# 3_BLE-T3-mcu.net
KiCad netlist of a schematic drawn in Altium Designer
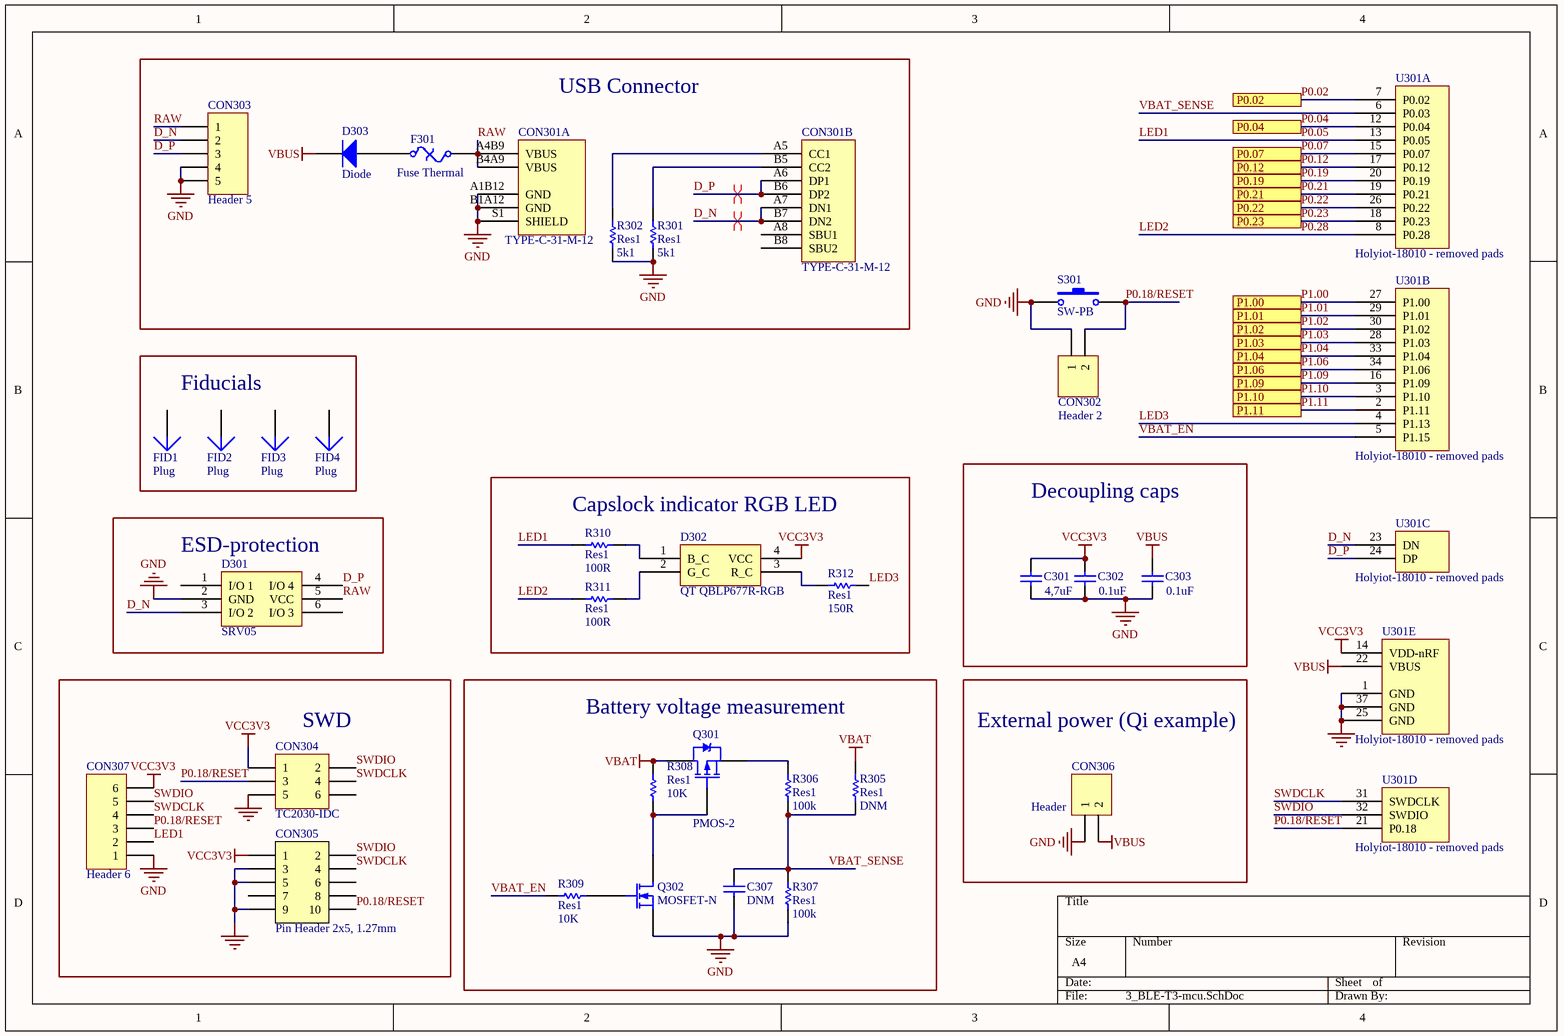
[diagram p0: 3_BLE-T3-mcu.SchDoc]

(export (version "E")
  (design (tool "Eeschema 10.0.6"))
  (components
    (comp (ref "C301")
      (value "4,7uF")
      (footprint "C0603[1608]")
      (description "Capacitor")
      (fields (field (name "LCSC PART #") "C19666") (field (name "MRF.PART") "CL10A475KO8NNNC"))
      (libsource (lib "Miscellaneous Devices") (part "Cap"))
    )
    (comp (ref "C302")
      (value "0.1uF")
      (footprint "C0603[1608]")
      (description "Capacitor")
      (fields (field (name "MFG") "KEMET") (field (name "LCSC PART #") "C14663"))
      (libsource (lib "Miscellaneous Devices") (part "Cap"))
    )
    (comp (ref "C303")
      (value "0.1uF")
      (footprint "C0603[1608]")
      (description "Capacitor")
      (fields (field (name "MFG") "KEMET") (field (name "LCSC PART #") "C14663"))
      (libsource (lib "Miscellaneous Devices") (part "Cap"))
    )
    (comp (ref "C307")
      (value "DNM")
      (footprint "C0603[1608]")
      (description "Capacitor")
      (libsource (lib "Miscellaneous Devices") (part "Cap"))
    )
    (comp (ref "CON301")
      (value "TYPE-C-31-M-12")
      (footprint "TYPE-C-31-M-12")
      (fields (field (name "MFG") "Korean Hroparts Elec") (field (name "LCSC PART #") "C165948"))
      (libsource (lib "Schlib1") (part "TYPE-C-31-M-12"))
    )
    (comp (ref "CON302")
      (value "Header 2")
      (footprint "HDR1X2")
      (description "Header, 2-Pin")
      (libsource (lib "") (part "Header 2_1"))
    )
    (comp (ref "CON303")
      (value "Header 5")
      (footprint "JST SM04B-SRSS-TB")
      (description "JST for USB daughter board")
      (fields (field (name "MFG") "JST Sales America Inc.") (field (name "LCSC PART #") "C160404"))
      (libsource (lib "Miscellaneous Connectors") (part "Header 5"))
    )
    (comp (ref "CON304")
      (value "TC2030-IDC")
      (footprint "TC2030-IDC-NL")
      (description "Header, 3-Pin, Dual row")
      (libsource (lib "Miscellaneous Connectors") (part "Header 3X2"))
    )
    (comp (ref "CON305")
      (value "Pin Header 2x5, 1.27mm")
      (footprint "HDR_2x5-SMD-1.27mm-K")
      (description "Pin Header 2x5, 1.27mm (50mil), SMD, Keying Shroud")
      (fields (field (name "MFG") "Samtec Inc."))
      (libsource (lib "Nordic Passive DB") (part "CONN-2x5"))
    )
    (comp (ref "CON306")
      (value "Header")
      (footprint "HDR1X2")
      (description "Header, 2-Pin")
      (libsource (lib "Miscellaneous Connectors") (part "Header 2"))
    )
    (comp (ref "CON307")
      (value "Header 6")
      (footprint "HDR1X6")
      (description "Header, 6-Pin")
      (fields (field (name "PUBLISHER") "Altium Limited"))
      (libsource (lib "Miscellaneous Connectors") (part "Header 6"))
    )
    (comp (ref "D301")
      (value "SRV05")
      (footprint "SOT-23-6")
      (fields (field (name "LCSC PART #") "C85364") (field (name "MRF.PART") "SRV05-4-P-T7"))
      (libsource (lib "Keebs") (part "SRV05"))
    )
    (comp (ref "D302")
      (value "QT QBLP677R-RGB")
      (footprint "QT QBLP677R-RGB")
      (description "RGB LED")
      (fields (field (name "MFG") "QT Brightek (QTB)"))
      (libsource (lib "Keebs") (part "QT QBLP677R-RGB"))
    )
    (comp (ref "D303")
      (value "Diode")
      (footprint "SOD-123")
      (description "Default Diode")
      (fields (field (name "LCSC PART #") "C8598") (field (name "MRF.PART") "B5819W"))
      (libsource (lib "Miscellaneous Devices") (part "Diode"))
    )
    (comp (ref "F301")
      (value "Fuse Thermal")
      (footprint "C1206[3216]")
      (description "Thermal Fuse")
      (fields (field (name "MFG") "Bel Fuse Inc.") (field (name "LCSC PART #") "C135338"))
      (libsource (lib "Miscellaneous Devices") (part "Fuse Thermal"))
    )
    (comp (ref "FID1")
      (value "Plug")
      (footprint "Fiducial_Nordic")
      (libsource (lib "Miscellaneous Connectors") (part "Plug"))
    )
    (comp (ref "FID2")
      (value "Plug")
      (footprint "Fiducial_Nordic")
      (libsource (lib "Miscellaneous Connectors") (part "Plug"))
    )
    (comp (ref "FID3")
      (value "Plug")
      (footprint "Fiducial_Nordic")
      (libsource (lib "Miscellaneous Connectors") (part "Plug"))
    )
    (comp (ref "FID4")
      (value "Plug")
      (footprint "Fiducial_Nordic")
      (libsource (lib "Miscellaneous Connectors") (part "Plug"))
    )
    (comp (ref "Q301")
      (value "PMOS-2")
      (footprint "SOT-23-3")
      (description "P-Channel Power MOSFET")
      (fields (field (name "MRF.PART") "SI2301CDS-T1-GE3") (field (name "LCSC PART #") "C10487"))
      (libsource (lib "Miscellaneous Devices") (part "PMOS-2"))
    )
    (comp (ref "Q302")
      (value "MOSFET-N")
      (footprint "SOT-23-3")
      (description "N-Channel MOSFET")
      (fields (field (name "LCSC PART #") "C8545") (field (name "MRF.PART") "2N7002"))
      (libsource (lib "Miscellaneous Devices") (part "MOSFET-N"))
    )
    (comp (ref "R301")
      (value "Res1")
      (footprint "R0603[1608]")
      (description "Resistor")
      (fields
        (field (name "ALTIUM_VALUE") "5k1")
        (field (name "MFG") "Panasonic Electronic Components")
        (field (name "LCSC PART #") "C23186")
      )
      (libsource (lib "Miscellaneous Devices") (part "Res1"))
    )
    (comp (ref "R302")
      (value "Res1")
      (footprint "R0603[1608]")
      (description "Resistor")
      (fields
        (field (name "ALTIUM_VALUE") "5k1")
        (field (name "MFG") "Panasonic Electronic Components")
        (field (name "LCSC PART #") "C23186")
      )
      (libsource (lib "Miscellaneous Devices") (part "Res1"))
    )
    (comp (ref "R305")
      (value "Res1")
      (footprint "R0603[1608]")
      (description "Resistor")
      (fields (field (name "ALTIUM_VALUE") "DNM"))
      (libsource (lib "Miscellaneous Devices") (part "Res1"))
    )
    (comp (ref "R306")
      (value "Res1")
      (footprint "R0603[1608]")
      (description "Resistor")
      (fields
        (field (name "ALTIUM_VALUE") "100k")
        (field (name "MRF.PART") "0603WAF1003T5E")
        (field (name "LCSC PART #") "C25803")
      )
      (libsource (lib "Miscellaneous Devices") (part "Res1"))
    )
    (comp (ref "R307")
      (value "Res1")
      (footprint "R0603[1608]")
      (description "Resistor")
      (fields
        (field (name "ALTIUM_VALUE") "100k")
        (field (name "MRF.PART") "0603WAF1003T5E")
        (field (name "LCSC PART #") "C25803")
      )
      (libsource (lib "Miscellaneous Devices") (part "Res1"))
    )
    (comp (ref "R308")
      (value "Res1")
      (footprint "R0603[1608]")
      (description "Resistor")
      (fields
        (field (name "ALTIUM_VALUE") "10K")
        (field (name "MFG") "Panasonic Electronic Components")
        (field (name "LCSC PART #") "C25804")
      )
      (libsource (lib "Miscellaneous Devices") (part "Res1"))
    )
    (comp (ref "R309")
      (value "Res1")
      (footprint "R0603[1608]")
      (description "Resistor")
      (fields
        (field (name "ALTIUM_VALUE") "10K")
        (field (name "MFG") "Panasonic Electronic Components")
        (field (name "LCSC PART #") "C25804")
      )
      (libsource (lib "Miscellaneous Devices") (part "Res1"))
    )
    (comp (ref "R310")
      (value "Res1")
      (footprint "R0603[1608]")
      (description "Resistor")
      (fields
        (field (name "ALTIUM_VALUE") "100R")
        (field (name "LCSC PART #") "C22775")
        (field (name "MRF.PART") "0603WAF1000T5E")
      )
      (libsource (lib "Miscellaneous Devices") (part "Res1"))
    )
    (comp (ref "R311")
      (value "Res1")
      (footprint "R0603[1608]")
      (description "Resistor")
      (fields
        (field (name "ALTIUM_VALUE") "100R")
        (field (name "LCSC PART #") "C22775")
        (field (name "MRF.PART") "0603WAF1000T5E")
      )
      (libsource (lib "Miscellaneous Devices") (part "Res1"))
    )
    (comp (ref "R312")
      (value "Res1")
      (footprint "R0603[1608]")
      (description "Resistor")
      (fields
        (field (name "ALTIUM_VALUE") "150R")
        (field (name "LCSC PART #") "C22808")
        (field (name "MRF.PART") "0603WAF1500T5E")
      )
      (libsource (lib "Miscellaneous Devices") (part "Res1"))
    )
    (comp (ref "S301")
      (value "SW-PB")
      (footprint "Combo switch")
      (description "Switch")
      (fields (field (name "MFG") "C&K") (field (name "MRF.PART") "TS-1187A-C-D-B"))
      (libsource (lib "Miscellaneous Devices") (part "SW-PB"))
    )
    (comp (ref "U301")
      (value "Holyiot-18010 - removed pads")
      (footprint "Holyiot-18010 - removed pads")
      (libsource (lib "Keebs") (part "Holyiot-18010 - removed pads"))
    )
  )
  (nets
    (net (code "1") (name "/D_N") (class "Default")
      (node (ref "CON301") (pin "A7") (pinfunction "DN1_A7") (pintype "passive"))
      (node (ref "CON301") (pin "B7") (pinfunction "DN2_B7") (pintype "passive"))
      (node (ref "CON303") (pin "2") (pinfunction "2_2") (pintype "passive"))
      (node (ref "D301") (pin "3") (pinfunction "I/O_2_3") (pintype "passive"))
      (node (ref "U301") (pin "23") (pinfunction "DN_23") (pintype "passive"))
    )
    (net (code "2") (name "/D_P") (class "Default")
      (node (ref "CON301") (pin "A6") (pinfunction "DP1_A6") (pintype "passive"))
      (node (ref "CON301") (pin "B6") (pinfunction "DP2_B6") (pintype "passive"))
      (node (ref "CON303") (pin "3") (pinfunction "3_3") (pintype "passive"))
      (node (ref "D301") (pin "4") (pinfunction "I/O_4_4") (pintype "passive"))
      (node (ref "U301") (pin "24") (pinfunction "DP_24") (pintype "passive"))
    )
    (net (code "3") (name "/LED1") (class "Default")
      (node (ref "CON307") (pin "2") (pinfunction "2_2") (pintype "passive"))
      (node (ref "R310") (pin "2") (pinfunction "2_2") (pintype "passive"))
      (node (ref "U301") (pin "13") (pinfunction "P0.05_13") (pintype "passive"))
    )
    (net (code "4") (name "/LED2") (class "Default")
      (node (ref "R311") (pin "2") (pinfunction "2_2") (pintype "passive"))
      (node (ref "U301") (pin "8") (pinfunction "P0.28_8") (pintype "passive"))
    )
    (net (code "5") (name "/LED3") (class "Default")
      (node (ref "R312") (pin "1") (pinfunction "1_1") (pintype "passive"))
      (node (ref "U301") (pin "4") (pinfunction "P1.13_4") (pintype "passive"))
    )
    (net (code "6") (name "/P0.02") (class "Default")
      (node (ref "U301") (pin "7") (pinfunction "P0.02_7") (pintype "passive"))
    )
    (net (code "7") (name "/P0.04") (class "Default")
      (node (ref "U301") (pin "12") (pinfunction "P0.04_12") (pintype "passive"))
    )
    (net (code "8") (name "/P0.07") (class "Default")
      (node (ref "U301") (pin "15") (pinfunction "P0.07_15") (pintype "passive"))
    )
    (net (code "9") (name "/P0.12") (class "Default")
      (node (ref "U301") (pin "17") (pinfunction "P0.12_17") (pintype "passive"))
    )
    (net (code "10") (name "/P0.18{slash}RESET") (class "Default")
      (node (ref "CON302") (pin "2") (pinfunction "2_2") (pintype "passive"))
      (node (ref "CON304") (pin "3") (pinfunction "3_3") (pintype "passive"))
      (node (ref "CON305") (pin "10") (pinfunction "10_10") (pintype "passive"))
      (node (ref "CON307") (pin "3") (pinfunction "3_3") (pintype "passive"))
      (node (ref "S301") (pin "2") (pinfunction "2_2") (pintype "passive"))
      (node (ref "U301") (pin "21") (pinfunction "P0.18_21") (pintype "passive"))
    )
    (net (code "11") (name "/P0.19") (class "Default")
      (node (ref "U301") (pin "20") (pinfunction "P0.19_20") (pintype "passive"))
    )
    (net (code "12") (name "/P0.21") (class "Default")
      (node (ref "U301") (pin "19") (pinfunction "P0.21_19") (pintype "passive"))
    )
    (net (code "13") (name "/P0.22") (class "Default")
      (node (ref "U301") (pin "26") (pinfunction "P0.22_26") (pintype "passive"))
    )
    (net (code "14") (name "/P0.23") (class "Default")
      (node (ref "U301") (pin "18") (pinfunction "P0.23_18") (pintype "passive"))
    )
    (net (code "15") (name "/P1.00") (class "Default")
      (node (ref "U301") (pin "27") (pinfunction "P1.00_27") (pintype "passive"))
    )
    (net (code "16") (name "/P1.01") (class "Default")
      (node (ref "U301") (pin "29") (pinfunction "P1.01_29") (pintype "passive"))
    )
    (net (code "17") (name "/P1.02") (class "Default")
      (node (ref "U301") (pin "30") (pinfunction "P1.02_30") (pintype "passive"))
    )
    (net (code "18") (name "/P1.03") (class "Default")
      (node (ref "U301") (pin "28") (pinfunction "P1.03_28") (pintype "passive"))
    )
    (net (code "19") (name "/P1.04") (class "Default")
      (node (ref "U301") (pin "33") (pinfunction "P1.04_33") (pintype "passive"))
    )
    (net (code "20") (name "/P1.06") (class "Default")
      (node (ref "U301") (pin "34") (pinfunction "P1.06_34") (pintype "passive"))
    )
    (net (code "21") (name "/P1.09") (class "Default")
      (node (ref "U301") (pin "16") (pinfunction "P1.09_16") (pintype "passive"))
    )
    (net (code "22") (name "/P1.10") (class "Default")
      (node (ref "U301") (pin "3") (pinfunction "P1.10_3") (pintype "passive"))
    )
    (net (code "23") (name "/P1.11") (class "Default")
      (node (ref "U301") (pin "2") (pinfunction "P1.11_2") (pintype "passive"))
    )
    (net (code "24") (name "/RAW") (class "Default")
      (node (ref "CON301") (pin "A4B9") (pinfunction "VBUS_A4B9") (pintype "passive"))
      (node (ref "CON301") (pin "B4A9") (pinfunction "VBUS_B4A9") (pintype "passive"))
      (node (ref "CON303") (pin "1") (pinfunction "1_1") (pintype "passive"))
      (node (ref "D301") (pin "5") (pinfunction "VCC_5") (pintype "passive"))
      (node (ref "F301") (pin "2") (pinfunction "2_2") (pintype "passive"))
    )
    (net (code "25") (name "/SWDCLK") (class "Default")
      (node (ref "CON304") (pin "4") (pinfunction "4_4") (pintype "passive"))
      (node (ref "CON305") (pin "4") (pinfunction "4_4") (pintype "passive"))
      (node (ref "CON307") (pin "4") (pinfunction "4_4") (pintype "passive"))
      (node (ref "U301") (pin "31") (pinfunction "SWDCLK_31") (pintype "passive"))
    )
    (net (code "26") (name "/SWDIO") (class "Default")
      (node (ref "CON304") (pin "2") (pinfunction "2_2") (pintype "passive"))
      (node (ref "CON305") (pin "2") (pinfunction "2_2") (pintype "passive"))
      (node (ref "CON307") (pin "5") (pinfunction "5_5") (pintype "passive"))
      (node (ref "U301") (pin "32") (pinfunction "SWDIO_32") (pintype "passive"))
    )
    (net (code "27") (name "/VBAT_EN") (class "Default")
      (node (ref "R309") (pin "1") (pinfunction "1_1") (pintype "passive"))
      (node (ref "U301") (pin "5") (pinfunction "P1.15_5") (pintype "passive"))
    )
    (net (code "28") (name "/VBAT_SENSE") (class "Default")
      (node (ref "C307") (pin "2") (pinfunction "2_2") (pintype "passive"))
      (node (ref "R305") (pin "1") (pinfunction "1_1") (pintype "passive"))
      (node (ref "R306") (pin "2") (pinfunction "2_2") (pintype "passive"))
      (node (ref "R307") (pin "1") (pinfunction "1_1") (pintype "passive"))
      (node (ref "U301") (pin "6") (pinfunction "P0.03_6") (pintype "passive"))
    )
    (net (code "29") (name "GND") (class "Default")
      (node (ref "C301") (pin "1") (pinfunction "1_1") (pintype "passive"))
      (node (ref "C302") (pin "1") (pinfunction "1_1") (pintype "passive"))
      (node (ref "C303") (pin "1") (pinfunction "1_1") (pintype "passive"))
      (node (ref "C307") (pin "1") (pinfunction "1_1") (pintype "passive"))
      (node (ref "CON301") (pin "A1B12") (pinfunction "GND_A1B12") (pintype "passive"))
      (node (ref "CON301") (pin "B1A12") (pinfunction "GND_B1A12") (pintype "passive"))
      (node (ref "CON301") (pin "S1") (pinfunction "SHIELD_S1") (pintype "passive"))
      (node (ref "CON302") (pin "1") (pinfunction "1_1") (pintype "passive"))
      (node (ref "CON303") (pin "4") (pinfunction "4_4") (pintype "passive"))
      (node (ref "CON303") (pin "5") (pinfunction "5_5") (pintype "passive"))
      (node (ref "CON304") (pin "5") (pinfunction "5_5") (pintype "passive"))
      (node (ref "CON305") (pin "3") (pinfunction "3_3") (pintype "passive"))
      (node (ref "CON305") (pin "5") (pinfunction "5_5") (pintype "passive"))
      (node (ref "CON305") (pin "9") (pinfunction "9_9") (pintype "passive"))
      (node (ref "CON306") (pin "1") (pinfunction "1_1") (pintype "passive"))
      (node (ref "CON307") (pin "1") (pinfunction "1_1") (pintype "passive"))
      (node (ref "D301") (pin "2") (pinfunction "GND_2") (pintype "passive"))
      (node (ref "Q302") (pin "2") (pinfunction "S_2") (pintype "passive"))
      (node (ref "R301") (pin "2") (pinfunction "2_2") (pintype "passive"))
      (node (ref "R302") (pin "2") (pinfunction "2_2") (pintype "passive"))
      (node (ref "R307") (pin "2") (pinfunction "2_2") (pintype "passive"))
      (node (ref "S301") (pin "1") (pinfunction "1_1") (pintype "passive"))
      (node (ref "U301") (pin "1") (pinfunction "GND_1") (pintype "passive"))
      (node (ref "U301") (pin "25") (pinfunction "GND_25") (pintype "passive"))
      (node (ref "U301") (pin "37") (pinfunction "GND_37") (pintype "passive"))
    )
    (net (code "30") (name "Net-(CON301B-CC1)") (class "Default")
      (node (ref "CON301") (pin "A5") (pinfunction "CC1_A5") (pintype "passive"))
      (node (ref "R302") (pin "1") (pinfunction "1_1") (pintype "passive"))
    )
    (net (code "31") (name "Net-(CON301B-CC2)") (class "Default")
      (node (ref "CON301") (pin "B5") (pinfunction "CC2_B5") (pintype "passive"))
      (node (ref "R301") (pin "1") (pinfunction "1_1") (pintype "passive"))
    )
    (net (code "32") (name "Net-(D302-B_C)") (class "Default")
      (node (ref "D302") (pin "1") (pinfunction "B_C_1") (pintype "passive"))
      (node (ref "R310") (pin "1") (pinfunction "1_1") (pintype "passive"))
    )
    (net (code "33") (name "Net-(D302-G_C)") (class "Default")
      (node (ref "D302") (pin "2") (pinfunction "G_C_2") (pintype "passive"))
      (node (ref "R311") (pin "1") (pinfunction "1_1") (pintype "passive"))
    )
    (net (code "34") (name "Net-(D302-R_C)") (class "Default")
      (node (ref "D302") (pin "3") (pinfunction "R_C_3") (pintype "passive"))
      (node (ref "R312") (pin "2") (pinfunction "2_2") (pintype "passive"))
    )
    (net (code "35") (name "Net-(D303-A)") (class "Default")
      (node (ref "D303") (pin "1") (pinfunction "A_1") (pintype "passive"))
      (node (ref "F301") (pin "1") (pinfunction "1_1") (pintype "passive"))
    )
    (net (code "36") (name "Net-(Q301-G)") (class "Default")
      (node (ref "Q301") (pin "1") (pinfunction "G_1") (pintype "passive"))
      (node (ref "Q302") (pin "3") (pinfunction "D_3") (pintype "passive"))
      (node (ref "R308") (pin "2") (pinfunction "2_2") (pintype "passive"))
    )
    (net (code "37") (name "Net-(Q301-S)") (class "Default")
      (node (ref "Q301") (pin "2") (pinfunction "S_2") (pintype "passive"))
      (node (ref "R306") (pin "1") (pinfunction "1_1") (pintype "passive"))
    )
    (net (code "38") (name "Net-(Q302-G)") (class "Default")
      (node (ref "Q302") (pin "1") (pinfunction "G_1") (pintype "passive"))
      (node (ref "R309") (pin "2") (pinfunction "2_2") (pintype "passive"))
    )
    (net (code "39") (name "VBAT") (class "Default")
      (node (ref "Q301") (pin "3") (pinfunction "D_3") (pintype "passive"))
      (node (ref "R305") (pin "2") (pinfunction "2_2") (pintype "passive"))
      (node (ref "R308") (pin "1") (pinfunction "1_1") (pintype "passive"))
    )
    (net (code "40") (name "VBUS") (class "Default")
      (node (ref "C303") (pin "2") (pinfunction "2_2") (pintype "passive"))
      (node (ref "CON306") (pin "2") (pinfunction "2_2") (pintype "passive"))
      (node (ref "D303") (pin "2") (pinfunction "K_2") (pintype "passive"))
      (node (ref "U301") (pin "22") (pinfunction "VBUS_22") (pintype "passive"))
    )
    (net (code "41") (name "VCC3V3") (class "Default")
      (node (ref "C301") (pin "2") (pinfunction "2_2") (pintype "passive"))
      (node (ref "C302") (pin "2") (pinfunction "2_2") (pintype "passive"))
      (node (ref "CON304") (pin "1") (pinfunction "1_1") (pintype "passive"))
      (node (ref "CON305") (pin "1") (pinfunction "1_1") (pintype "passive"))
      (node (ref "CON307") (pin "6") (pinfunction "6_6") (pintype "passive"))
      (node (ref "D302") (pin "4") (pinfunction "VCC_4") (pintype "passive"))
      (node (ref "U301") (pin "14") (pinfunction "VDD-nRF_14") (pintype "passive"))
    )
    (net (code "42") (name "unconnected-(CON301B-SBU1-PadA8)") (class "Default")
      (node (ref "CON301") (pin "A8") (pinfunction "SBU1_A8") (pintype "passive"))
    )
    (net (code "43") (name "unconnected-(CON301B-SBU2-PadB8)") (class "Default")
      (node (ref "CON301") (pin "B8") (pinfunction "SBU2_B8") (pintype "passive"))
    )
    (net (code "44") (name "unconnected-(CON304-Pad6)") (class "Default")
      (node (ref "CON304") (pin "6") (pinfunction "6_6") (pintype "passive"))
    )
    (net (code "45") (name "unconnected-(CON305-Pad6)") (class "Default")
      (node (ref "CON305") (pin "6") (pinfunction "6_6") (pintype "passive"))
    )
    (net (code "46") (name "unconnected-(CON305-Pad7)") (class "Default")
      (node (ref "CON305") (pin "7") (pinfunction "7_7") (pintype "passive"))
    )
    (net (code "47") (name "unconnected-(CON305-Pad8)") (class "Default")
      (node (ref "CON305") (pin "8") (pinfunction "8_8") (pintype "passive"))
    )
    (net (code "48") (name "unconnected-(D301-I{slash}O_1-Pad1)") (class "Default")
      (node (ref "D301") (pin "1") (pinfunction "I/O_1_1") (pintype "passive"))
    )
    (net (code "49") (name "unconnected-(D301-I{slash}O_3-Pad6)") (class "Default")
      (node (ref "D301") (pin "6") (pinfunction "I/O_3_6") (pintype "passive"))
    )
    (net (code "50") (name "unconnected-(FID1-Pad1)") (class "Default")
      (node (ref "FID1") (pin "1") (pinfunction "1_1") (pintype "passive"))
    )
    (net (code "51") (name "unconnected-(FID2-Pad1)") (class "Default")
      (node (ref "FID2") (pin "1") (pinfunction "1_1") (pintype "passive"))
    )
    (net (code "52") (name "unconnected-(FID3-Pad1)") (class "Default")
      (node (ref "FID3") (pin "1") (pinfunction "1_1") (pintype "passive"))
    )
    (net (code "53") (name "unconnected-(FID4-Pad1)") (class "Default")
      (node (ref "FID4") (pin "1") (pinfunction "1_1") (pintype "passive"))
    )
  )
)
